# RFM12B-V1_2.net
KiCad netlist of a schematic drawn in EAGLE
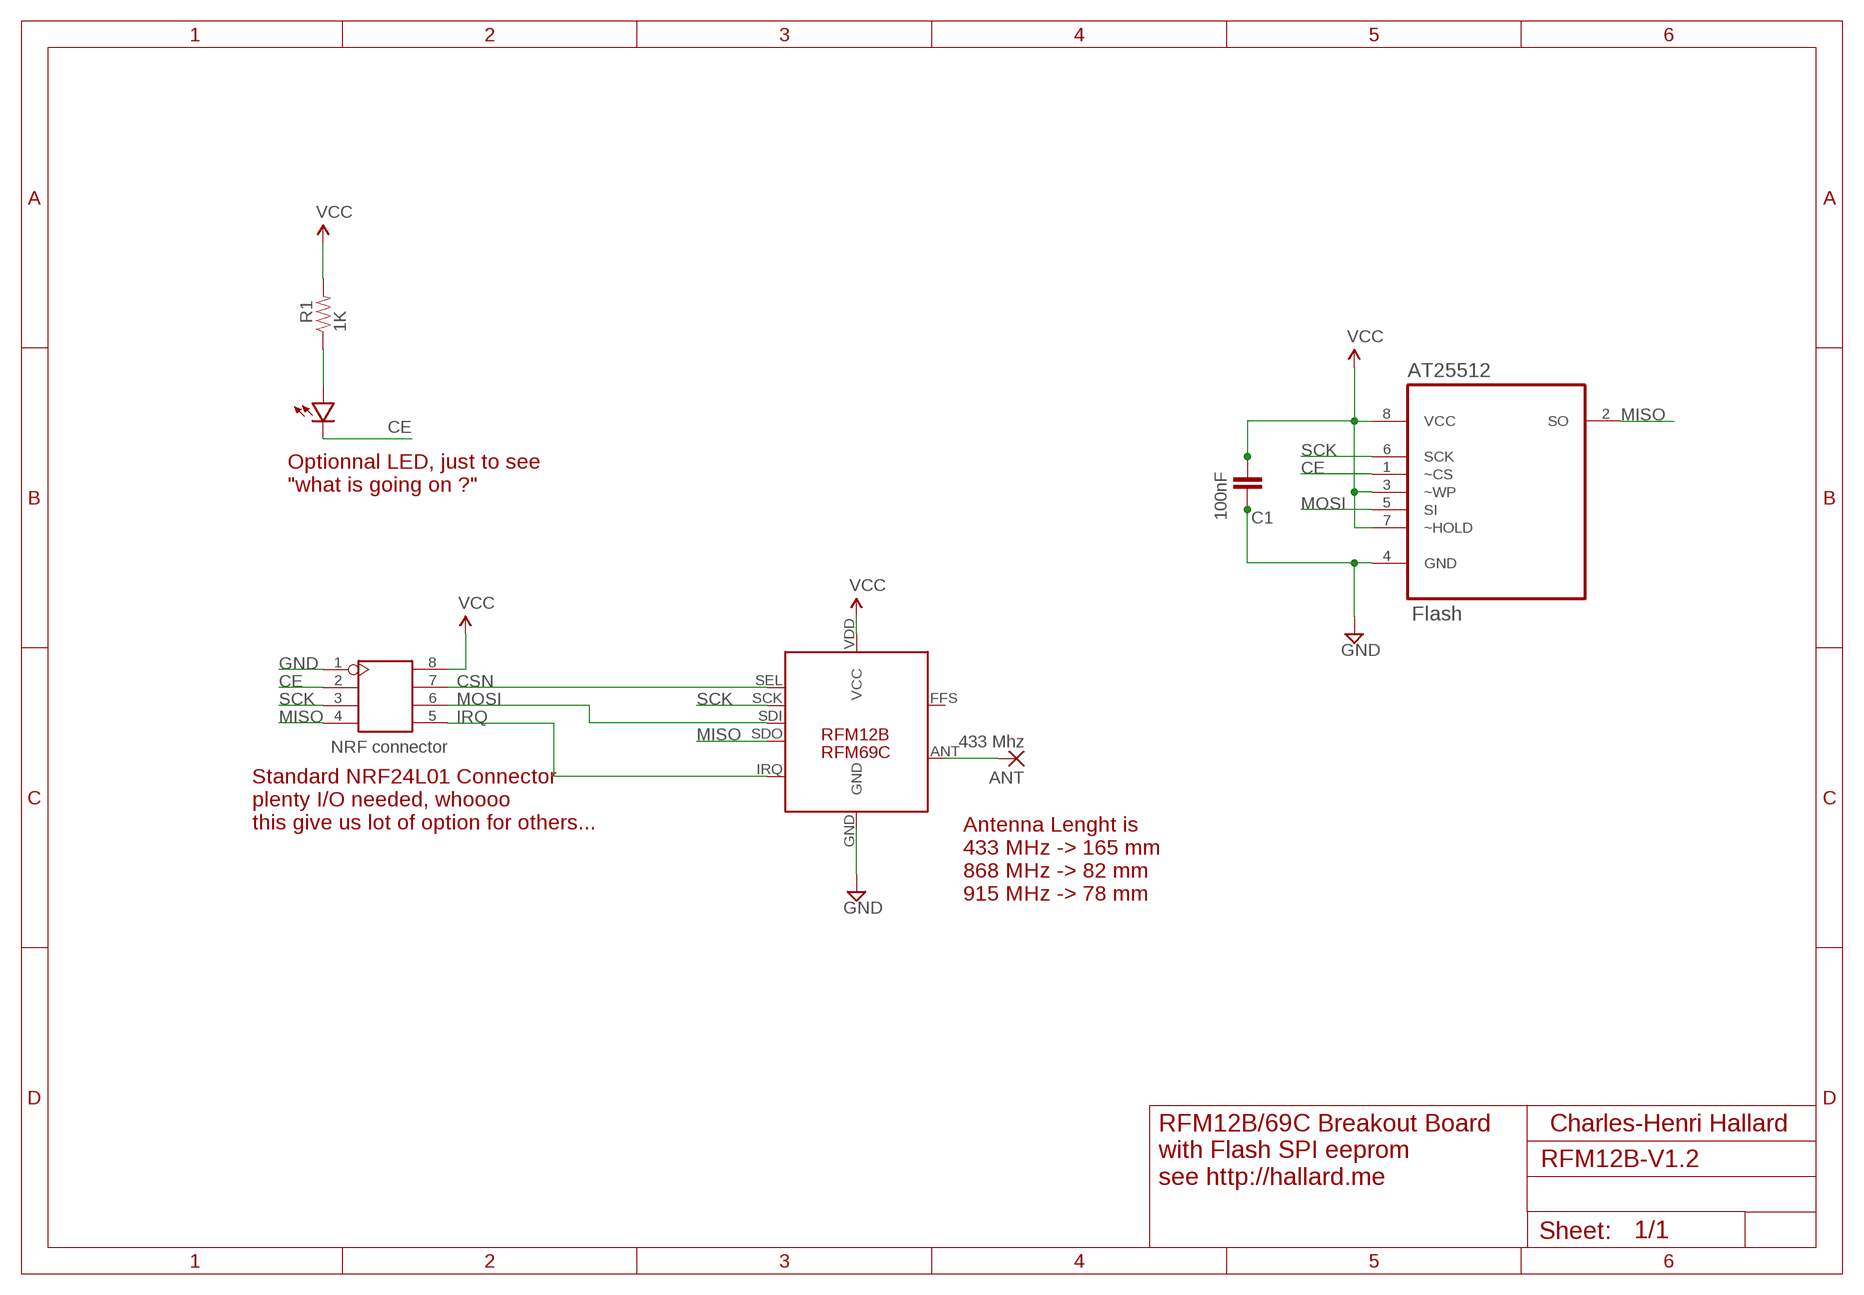
[diagram p0: schematic, sheet 1]

(export (version "E")
  (design (tool "Eeschema 10.0.6"))
  (components
    (comp (ref "ANT")
      (value "433 Mhz")
      (footprint "eagle-import:1,6_0,8")
      (libsource (lib "eagle-import") (part "1,6/0,8"))
    )
    (comp (ref "AT25512")
      (value "Flash")
      (footprint "eagle-import:SOIC127P600X175-8N")
      (fields (field (name "MPN") "AT25512N-SH-B"))
      (libsource (lib "eagle-import") (part "AT25512N-SH-B"))
    )
    (comp (ref "C1")
      (value "100nF")
      (footprint "eagle-import:0805-CAP")
      (libsource (lib "eagle-import") (part "CAP0805-CAP"))
    )
    (comp (ref "J1")
      (value "NRF connector")
      (footprint "eagle-import:2X4P-2.54")
      (libsource (lib "eagle-import") (part "HEADER-2X4P-2.54"))
    )
    (comp (ref "R1")
      (value "1K")
      (footprint "eagle-import:0805-RES")
      (libsource (lib "eagle-import") (part "RESISTOR0805-RES"))
    )
    (comp (ref "U$1")
      (value "LED0805-LARGE")
      (footprint "eagle-import:0805-LED-LARGEPADS")
      (libsource (lib "eagle-import") (part "LED0805-LARGE"))
    )
    (comp (ref "U$2")
      (value "RFM12B")
      (footprint "eagle-import:RFM12B")
      (libsource (lib "eagle-import") (part "RFM12B"))
    )
  )
  (nets
    (net (code "1") (name "/CE") (class "Default")
      (node (ref "AT25512") (pin "1") (pinfunction "~{CS}_1") (pintype "input"))
      (node (ref "J1") (pin "2") (pinfunction "2_2") (pintype "bidirectional"))
      (node (ref "U$1") (pin "MINUS") (pinfunction "MINUS_MINUS") (pintype "passive"))
    )
    (net (code "2") (name "/CSN") (class "Default")
      (node (ref "J1") (pin "7") (pinfunction "7_7") (pintype "bidirectional"))
      (node (ref "U$2") (pin "SEL") (pinfunction "SEL_SEL") (pintype "input"))
    )
    (net (code "3") (name "/IRQ") (class "Default")
      (node (ref "J1") (pin "5") (pinfunction "5_5") (pintype "bidirectional"))
      (node (ref "U$2") (pin "IRQ") (pinfunction "IRQ_IRQ") (pintype "open_collector"))
    )
    (net (code "4") (name "/MISO") (class "Default")
      (node (ref "AT25512") (pin "2") (pinfunction "SO_2") (pintype "output"))
      (node (ref "J1") (pin "4") (pinfunction "4_4") (pintype "bidirectional"))
      (node (ref "U$2") (pin "SDO") (pinfunction "SDO_SDO") (pintype "output"))
    )
    (net (code "5") (name "/MOSI") (class "Default")
      (node (ref "AT25512") (pin "5") (pinfunction "SI_5") (pintype "input"))
      (node (ref "J1") (pin "6") (pinfunction "6_6") (pintype "bidirectional"))
      (node (ref "U$2") (pin "SDI") (pinfunction "SDI_SDI") (pintype "input"))
    )
    (net (code "6") (name "/SCK") (class "Default")
      (node (ref "AT25512") (pin "6") (pinfunction "SCK_6") (pintype "input"))
      (node (ref "J1") (pin "3") (pinfunction "3_3") (pintype "bidirectional"))
      (node (ref "U$2") (pin "SCK") (pinfunction "SCK_SCK") (pintype "input"))
    )
    (net (code "7") (name "GND") (class "Default")
      (node (ref "AT25512") (pin "4") (pinfunction "GND_4") (pintype "passive"))
      (node (ref "C1") (pin "2") (pinfunction "2_2") (pintype "passive"))
      (node (ref "J1") (pin "1") (pinfunction "1_1") (pintype "bidirectional"))
      (node (ref "U$2") (pin "GND") (pinfunction "GND_GND") (pintype "power_in"))
    )
    (net (code "8") (name "Net-(ANT-P)") (class "Default")
      (node (ref "ANT") (pin "1") (pinfunction "P_1") (pintype "passive"))
      (node (ref "U$2") (pin "ANT") (pinfunction "ANT_ANT") (pintype "passive"))
    )
    (net (code "9") (name "Net-(R1-Pad1)") (class "Default")
      (node (ref "R1") (pin "1") (pinfunction "1_1") (pintype "passive"))
      (node (ref "U$1") (pin "PLUS") (pinfunction "PLUS_PLUS") (pintype "passive"))
    )
    (net (code "10") (name "VCC") (class "Default")
      (node (ref "AT25512") (pin "3") (pinfunction "~{WP}_3") (pintype "input"))
      (node (ref "AT25512") (pin "7") (pinfunction "~{HOLD}_7") (pintype "input"))
      (node (ref "AT25512") (pin "8") (pinfunction "VCC_8") (pintype "power_in"))
      (node (ref "C1") (pin "1") (pinfunction "1_1") (pintype "passive"))
      (node (ref "J1") (pin "8") (pinfunction "8_8") (pintype "bidirectional"))
      (node (ref "R1") (pin "2") (pinfunction "2_2") (pintype "passive"))
      (node (ref "U$2") (pin "VDD") (pinfunction "VCC_VDD") (pintype "power_in"))
    )
    (net (code "11") (name "unconnected-(U$2-PadFFS)") (class "Default")
      (node (ref "U$2") (pin "FFS") (pinfunction "FFS_FFS") (pintype "bidirectional"))
    )
  )
)
